# DomOS_V2.net
KiCad netlist of a schematic drawn in EAGLE
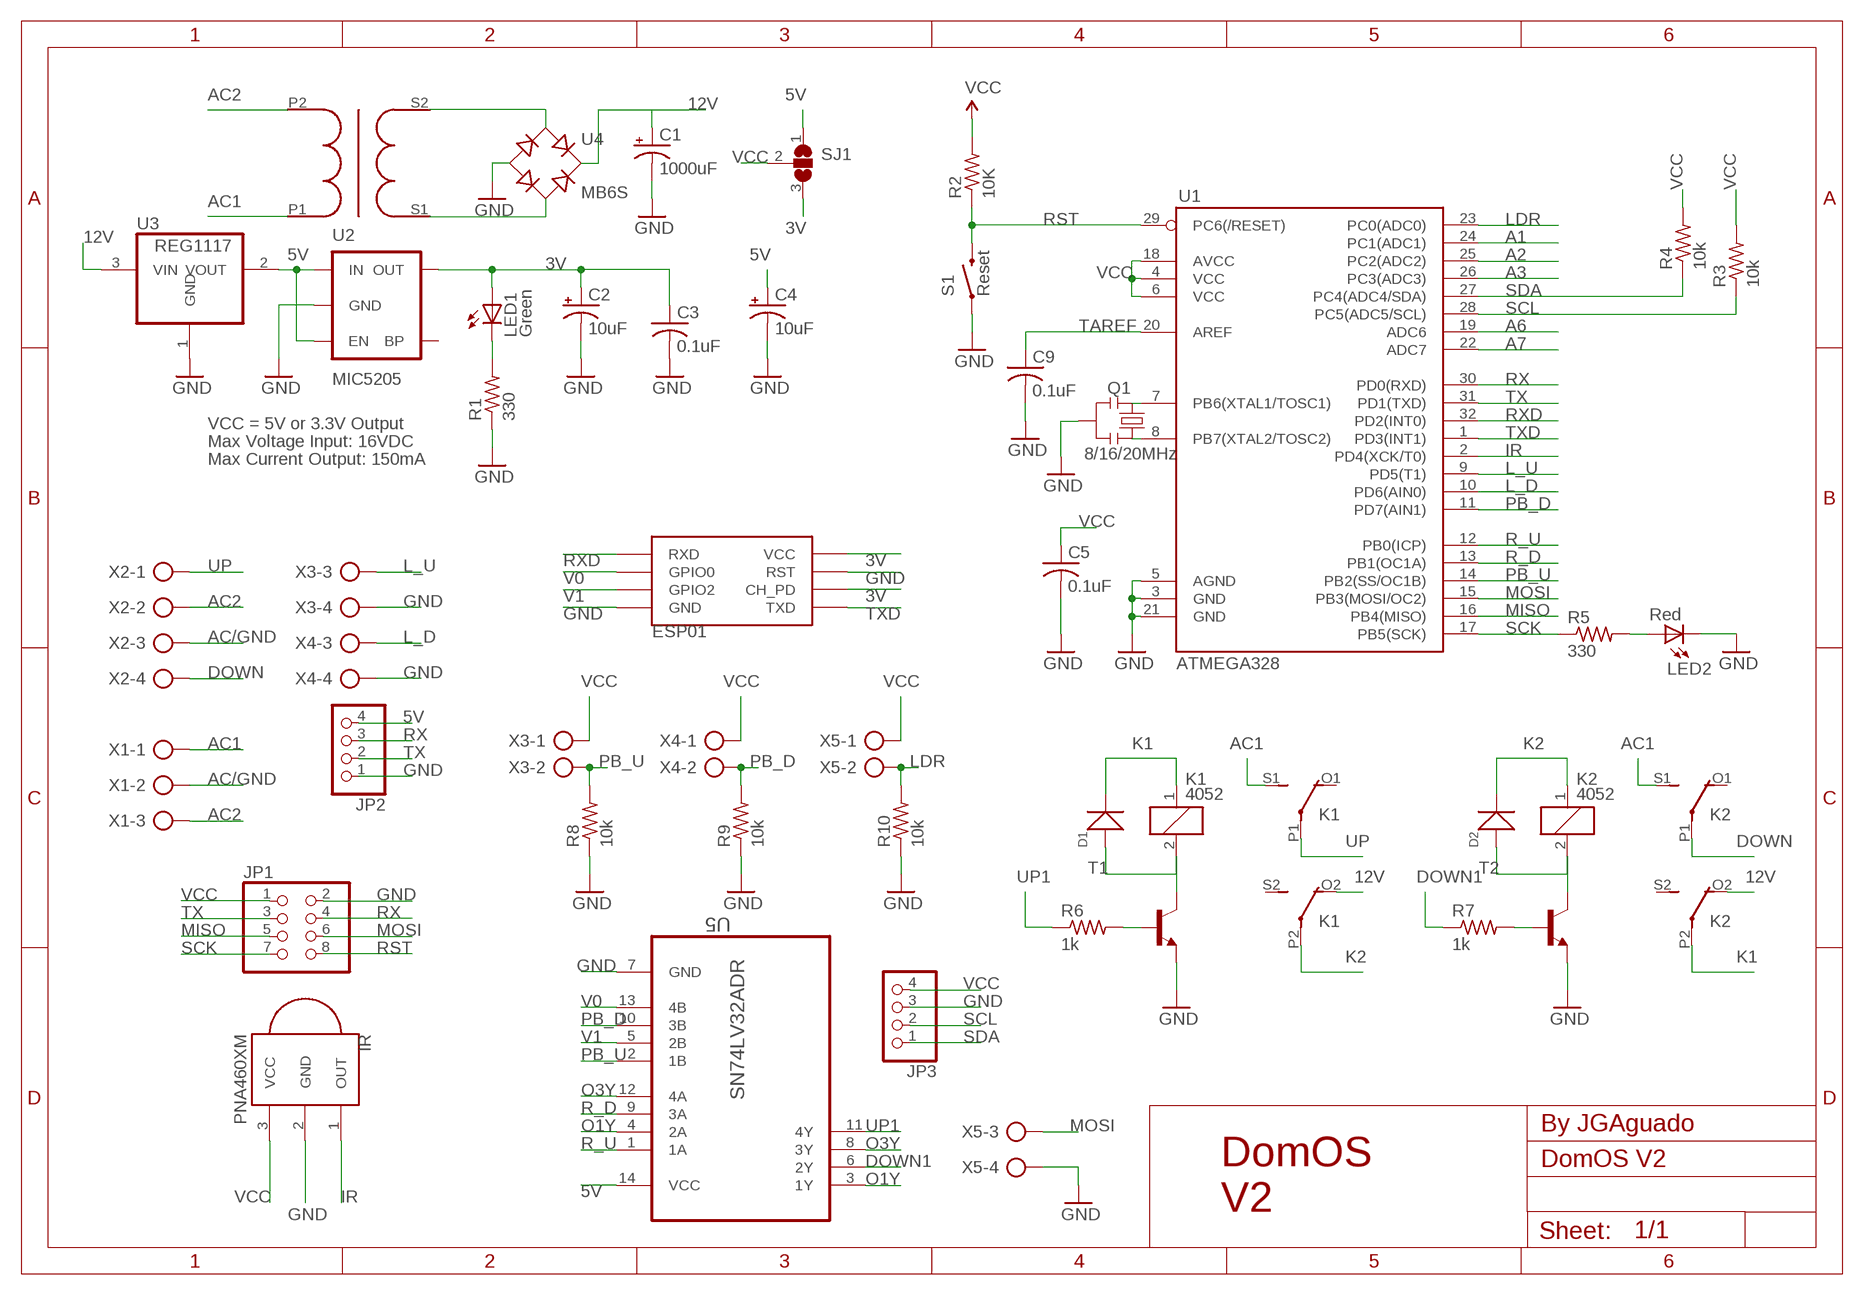
[diagram p0: schematic, sheet 1]

(export (version "E")
  (design (tool "Eeschema 10.0.6"))
  (components
    (comp (ref "C1")
      (value "1000uF")
      (footprint "eagle-import:140CLH-0810")
      (libsource (lib "eagle-import") (part "CPOL-US140CLH-0810"))
    )
    (comp (ref "C2")
      (value "10uF")
      (footprint "eagle-import:EIA3216")
      (libsource (lib "eagle-import") (part "CAP_POL1206"))
    )
    (comp (ref "C3")
      (value "0.1uF")
      (footprint "eagle-import:C1206")
      (libsource (lib "eagle-import") (part "C-USC1206"))
    )
    (comp (ref "C4")
      (value "10uF")
      (footprint "eagle-import:EIA3216")
      (libsource (lib "eagle-import") (part "CAP_POL1206"))
    )
    (comp (ref "C5")
      (value "0.1uF")
      (footprint "eagle-import:C1206")
      (libsource (lib "eagle-import") (part "C-USC1206"))
    )
    (comp (ref "C9")
      (value "0.1uF")
      (footprint "eagle-import:C1206")
      (libsource (lib "eagle-import") (part "C-USC1206"))
    )
    (comp (ref "D1")
      (value "SMD-DIODE-SWITCHING-75V-150MA(D1206)")
      (footprint "eagle-import:LED-1206")
      (fields (field (name "MPN") "CD1206-S01575"))
      (libsource (lib "eagle-import") (part "SMD-DIODE-SWITCHING-75V-150MA(D1206)"))
    )
    (comp (ref "D2")
      (value "SMD-DIODE-SWITCHING-75V-150MA(D1206)")
      (footprint "eagle-import:LED-1206")
      (fields (field (name "MPN") "CD1206-S01575"))
      (libsource (lib "eagle-import") (part "SMD-DIODE-SWITCHING-75V-150MA(D1206)"))
    )
    (comp (ref "ESP01")
      (value "ESP01")
      (footprint "eagle-import:ESP01")
      (libsource (lib "eagle-import") (part "ESP01"))
    )
    (comp (ref "IR")
      (value "PNA460XM")
      (footprint "eagle-import:PNA460XM")
      (libsource (lib "eagle-import") (part "PNA460XM"))
    )
    (comp (ref "JP1")
      (value "PINHD-2X4")
      (footprint "eagle-import:2X04")
      (libsource (lib "eagle-import") (part "PINHD-2X4"))
    )
    (comp (ref "JP2")
      (value "PINHD-1X4")
      (footprint "eagle-import:1X04")
      (libsource (lib "eagle-import") (part "PINHD-1X4"))
    )
    (comp (ref "JP3")
      (value "PINHD-1X4")
      (footprint "eagle-import:1X04")
      (libsource (lib "eagle-import") (part "PINHD-1X4"))
    )
    (comp (ref "K1")
      (value "4052")
      (footprint "eagle-import:F4052")
      (libsource (lib "eagle-import") (part "4052"))
    )
    (comp (ref "K2")
      (value "4052")
      (footprint "eagle-import:F4052")
      (libsource (lib "eagle-import") (part "4052"))
    )
    (comp (ref "LED1")
      (value "Green")
      (footprint "eagle-import:1206")
      (libsource (lib "eagle-import") (part "LEDSMT1206"))
    )
    (comp (ref "LED2")
      (value "Red")
      (footprint "eagle-import:1206")
      (libsource (lib "eagle-import") (part "LEDSMT1206"))
    )
    (comp (ref "Q1")
      (value "8/16/20MHz")
      (footprint "eagle-import:RESONATOR-SMD")
      (libsource (lib "eagle-import") (part "RESONATORSMD"))
    )
    (comp (ref "R1")
      (value "330")
      (footprint "eagle-import:R1206")
      (libsource (lib "eagle-import") (part "R-US_R1206"))
    )
    (comp (ref "R2")
      (value "10K")
      (footprint "eagle-import:R1206")
      (libsource (lib "eagle-import") (part "R-US_R1206"))
    )
    (comp (ref "R3")
      (value "10k")
      (footprint "eagle-import:R1206")
      (libsource (lib "eagle-import") (part "R-US_R1206"))
    )
    (comp (ref "R4")
      (value "10k")
      (footprint "eagle-import:R1206")
      (libsource (lib "eagle-import") (part "R-US_R1206"))
    )
    (comp (ref "R5")
      (value "330")
      (footprint "eagle-import:R1206")
      (libsource (lib "eagle-import") (part "R-US_R1206"))
    )
    (comp (ref "R6")
      (value "1k")
      (footprint "eagle-import:R1206")
      (libsource (lib "eagle-import") (part "R-US_R1206"))
    )
    (comp (ref "R7")
      (value "1k")
      (footprint "eagle-import:R1206")
      (libsource (lib "eagle-import") (part "R-US_R1206"))
    )
    (comp (ref "R8")
      (value "10k")
      (footprint "eagle-import:R1206")
      (libsource (lib "eagle-import") (part "R-US_R1206"))
    )
    (comp (ref "R9")
      (value "10k")
      (footprint "eagle-import:R1206")
      (libsource (lib "eagle-import") (part "R-US_R1206"))
    )
    (comp (ref "R10")
      (value "10k")
      (footprint "eagle-import:R1206")
      (libsource (lib "eagle-import") (part "R-US_R1206"))
    )
    (comp (ref "S1")
      (value "Reset")
      (footprint "eagle-import:TACTILE_SWITCH_TALL")
      (libsource (lib "eagle-import") (part "SWITCH-MOMENTARY-2SMD-4"))
    )
    (comp (ref "SJ1")
      (value "SJ2W")
      (footprint "eagle-import:SJ_2")
      (libsource (lib "eagle-import") (part "SJ2W"))
    )
    (comp (ref "T1")
      (value "BC817-16-NPN-SOT23-BEC")
      (footprint "eagle-import:SOT23-BEC")
      (libsource (lib "eagle-import") (part "-NPN-SOT23-BECBC817-16"))
    )
    (comp (ref "T2")
      (value "BC817-16-NPN-SOT23-BEC")
      (footprint "eagle-import:SOT23-BEC")
      (libsource (lib "eagle-import") (part "-NPN-SOT23-BECBC817-16"))
    )
    (comp (ref "U$1")
      (value "TRANSFORMADOR_PE3010-M")
      (footprint "eagle-import:TRANSFORMADOR_PE3010-M")
      (libsource (lib "eagle-import") (part "TRANSFORMADOR_PE3010-M"))
    )
    (comp (ref "U1")
      (value "ATMEGA328")
      (footprint "eagle-import:TQFP32-08")
      (libsource (lib "eagle-import") (part "ATMEGA168"))
    )
    (comp (ref "U2")
      (value "MIC5205")
      (footprint "eagle-import:SOT23-5")
      (libsource (lib "eagle-import") (part "V_REG_LDOSMD"))
    )
    (comp (ref "U3")
      (value "REG1117")
      (footprint "eagle-import:SOT223")
      (libsource (lib "eagle-import") (part "REG1117"))
    )
    (comp (ref "U4")
      (value "MB6S")
      (footprint "eagle-import:SOIC-4")
      (libsource (lib "eagle-import") (part "MBS6"))
    )
    (comp (ref "U5")
      (value "SN74LV32ADR")
      (footprint "eagle-import:SOIC127P600X175-14N")
      (fields (field (name "MPN") "SN74S32D"))
      (libsource (lib "eagle-import") (part "SN74S32D"))
    )
    (comp (ref "X1")
      (value "AK500/3")
      (footprint "eagle-import:AK500_3")
      (libsource (lib "eagle-import") (part "AK500/3"))
    )
    (comp (ref "X2")
      (value "AK500/4")
      (footprint "eagle-import:AK500_4")
      (libsource (lib "eagle-import") (part "AK500/4"))
    )
    (comp (ref "X3")
      (value "AK500/4")
      (footprint "eagle-import:AK500_4")
      (libsource (lib "eagle-import") (part "AK500/4"))
    )
    (comp (ref "X4")
      (value "AK500/4")
      (footprint "eagle-import:AK500_4")
      (libsource (lib "eagle-import") (part "AK500/4"))
    )
    (comp (ref "X5")
      (value "AK500/4")
      (footprint "eagle-import:AK500_4")
      (libsource (lib "eagle-import") (part "AK500/4"))
    )
  )
  (nets
    (net (code "1") (name "/3V") (class "Default")
      (node (ref "C2") (pin "A") (pinfunction "+_A") (pintype "passive"))
      (node (ref "C3") (pin "1") (pinfunction "1_1") (pintype "passive"))
      (node (ref "ESP01") (pin "CH_PD") (pinfunction "CH_PD_CH_PD") (pintype "bidirectional"))
      (node (ref "ESP01") (pin "VCC") (pinfunction "VCC_VCC") (pintype "bidirectional"))
      (node (ref "LED1") (pin "A") (pinfunction "A_A") (pintype "passive"))
      (node (ref "SJ1") (pin "3") (pinfunction "3_3") (pintype "passive"))
      (node (ref "U2") (pin "5") (pinfunction "OUT_5") (pintype "passive"))
    )
    (net (code "2") (name "/5V") (class "Default")
      (node (ref "C4") (pin "A") (pinfunction "+_A") (pintype "passive"))
      (node (ref "JP2") (pin "4") (pinfunction "4_4") (pintype "passive"))
      (node (ref "SJ1") (pin "1") (pinfunction "1_1") (pintype "passive"))
      (node (ref "U2") (pin "1") (pinfunction "IN_1") (pintype "input"))
      (node (ref "U2") (pin "3") (pinfunction "EN_3") (pintype "input"))
      (node (ref "U3") (pin "2") (pinfunction "VOUT_2") (pintype "output"))
      (node (ref "U5") (pin "14") (pinfunction "VCC_14") (pintype "power_in"))
    )
    (net (code "3") (name "/12V") (class "Default")
      (node (ref "C1") (pin "+") (pinfunction "+_+") (pintype "passive"))
      (node (ref "K1") (pin "O2") (pinfunction "O_O2") (pintype "passive"))
      (node (ref "K2") (pin "O2") (pinfunction "O_O2") (pintype "passive"))
      (node (ref "U3") (pin "3") (pinfunction "VIN_3") (pintype "input"))
      (node (ref "U4") (pin "+") (pinfunction "+_+") (pintype "passive"))
    )
    (net (code "4") (name "/A1") (class "Default")
      (node (ref "U1") (pin "24") (pinfunction "PC1(ADC1)_24") (pintype "bidirectional"))
    )
    (net (code "5") (name "/A2") (class "Default")
      (node (ref "U1") (pin "25") (pinfunction "PC2(ADC2)_25") (pintype "bidirectional"))
    )
    (net (code "6") (name "/A3") (class "Default")
      (node (ref "U1") (pin "26") (pinfunction "PC3(ADC3)_26") (pintype "bidirectional"))
    )
    (net (code "7") (name "/A6") (class "Default")
      (node (ref "U1") (pin "19") (pinfunction "ADC6_19") (pintype "bidirectional"))
    )
    (net (code "8") (name "/A7") (class "Default")
      (node (ref "U1") (pin "22") (pinfunction "ADC7_22") (pintype "bidirectional"))
    )
    (net (code "9") (name "/AC1") (class "Default")
      (node (ref "K1") (pin "S1") (pinfunction "S_S1") (pintype "passive"))
      (node (ref "K2") (pin "S1") (pinfunction "S_S1") (pintype "passive"))
      (node (ref "U$1") (pin "P1") (pinfunction "P1_P1") (pintype "bidirectional"))
      (node (ref "X1") (pin "1") (pinfunction "KL_1") (pintype "passive"))
    )
    (net (code "10") (name "/AC2") (class "Default")
      (node (ref "U$1") (pin "P2") (pinfunction "P2_P2") (pintype "bidirectional"))
      (node (ref "X1") (pin "3") (pinfunction "KL_3") (pintype "passive"))
      (node (ref "X2") (pin "2") (pinfunction "KL_2") (pintype "passive"))
    )
    (net (code "11") (name "/AC{slash}GND") (class "Default")
      (node (ref "X1") (pin "2") (pinfunction "KL_2") (pintype "passive"))
      (node (ref "X2") (pin "3") (pinfunction "KL_3") (pintype "passive"))
    )
    (net (code "12") (name "/DOWN") (class "Default")
      (node (ref "K2") (pin "P1") (pinfunction "P_P1") (pintype "passive"))
      (node (ref "X2") (pin "4") (pinfunction "KL_4") (pintype "passive"))
    )
    (net (code "13") (name "/DOWN1") (class "Default")
      (node (ref "R7") (pin "1") (pinfunction "1_1") (pintype "passive"))
      (node (ref "U5") (pin "6") (pinfunction "2Y_6") (pintype "output"))
    )
    (net (code "14") (name "/IR") (class "Default")
      (node (ref "IR") (pin "1") (pinfunction "OUT_1") (pintype "output"))
      (node (ref "U1") (pin "2") (pinfunction "PD4(XCK/T0)_2") (pintype "bidirectional"))
    )
    (net (code "15") (name "/K1") (class "Default")
      (node (ref "D1") (pin "-") (pinfunction "-_-") (pintype "passive"))
      (node (ref "K1") (pin "1") (pinfunction "1_1") (pintype "passive"))
      (node (ref "K2") (pin "P2") (pinfunction "P_P2") (pintype "passive"))
    )
    (net (code "16") (name "/K2") (class "Default")
      (node (ref "D2") (pin "-") (pinfunction "-_-") (pintype "passive"))
      (node (ref "K1") (pin "P2") (pinfunction "P_P2") (pintype "passive"))
      (node (ref "K2") (pin "1") (pinfunction "1_1") (pintype "passive"))
    )
    (net (code "17") (name "/LDR") (class "Default")
      (node (ref "R10") (pin "2") (pinfunction "2_2") (pintype "passive"))
      (node (ref "U1") (pin "23") (pinfunction "PC0(ADC0)_23") (pintype "bidirectional"))
      (node (ref "X5") (pin "2") (pinfunction "KL_2") (pintype "passive"))
    )
    (net (code "18") (name "/L_D") (class "Default")
      (node (ref "U1") (pin "10") (pinfunction "PD6(AIN0)_10") (pintype "bidirectional"))
      (node (ref "X4") (pin "3") (pinfunction "KL_3") (pintype "passive"))
    )
    (net (code "19") (name "/L_U") (class "Default")
      (node (ref "U1") (pin "9") (pinfunction "PD5(T1)_9") (pintype "bidirectional"))
      (node (ref "X3") (pin "3") (pinfunction "KL_3") (pintype "passive"))
    )
    (net (code "20") (name "/MISO") (class "Default")
      (node (ref "JP1") (pin "5") (pinfunction "5_5") (pintype "passive"))
      (node (ref "U1") (pin "16") (pinfunction "PB4(MISO)_16") (pintype "bidirectional"))
    )
    (net (code "21") (name "/MOSI") (class "Default")
      (node (ref "JP1") (pin "6") (pinfunction "6_6") (pintype "passive"))
      (node (ref "U1") (pin "15") (pinfunction "PB3(MOSI/OC2)_15") (pintype "bidirectional"))
      (node (ref "X5") (pin "3") (pinfunction "KL_3") (pintype "passive"))
    )
    (net (code "22") (name "/O1Y") (class "Default")
      (node (ref "U5") (pin "3") (pinfunction "1Y_3") (pintype "output"))
      (node (ref "U5") (pin "4") (pinfunction "2A_4") (pintype "input"))
    )
    (net (code "23") (name "/O3Y") (class "Default")
      (node (ref "U5") (pin "12") (pinfunction "4A_12") (pintype "input"))
      (node (ref "U5") (pin "8") (pinfunction "3Y_8") (pintype "output"))
    )
    (net (code "24") (name "/PB_D") (class "Default")
      (node (ref "R9") (pin "2") (pinfunction "2_2") (pintype "passive"))
      (node (ref "U1") (pin "11") (pinfunction "PD7(AIN1)_11") (pintype "bidirectional"))
      (node (ref "U5") (pin "10") (pinfunction "3B_10") (pintype "input"))
      (node (ref "X4") (pin "2") (pinfunction "KL_2") (pintype "passive"))
    )
    (net (code "25") (name "/PB_U") (class "Default")
      (node (ref "R8") (pin "2") (pinfunction "2_2") (pintype "passive"))
      (node (ref "U1") (pin "14") (pinfunction "PB2(SS/OC1B)_14") (pintype "bidirectional"))
      (node (ref "U5") (pin "2") (pinfunction "1B_2") (pintype "input"))
      (node (ref "X3") (pin "2") (pinfunction "KL_2") (pintype "passive"))
    )
    (net (code "26") (name "/RST") (class "Default")
      (node (ref "JP1") (pin "8") (pinfunction "8_8") (pintype "passive"))
      (node (ref "R2") (pin "1") (pinfunction "1_1") (pintype "passive"))
      (node (ref "S1") (pin "B2") (pinfunction "2_B2") (pintype "passive"))
      (node (ref "U1") (pin "29") (pinfunction "PC6(/RESET)_29") (pintype "bidirectional"))
    )
    (net (code "27") (name "/RX") (class "Default")
      (node (ref "JP1") (pin "4") (pinfunction "4_4") (pintype "passive"))
      (node (ref "JP2") (pin "3") (pinfunction "3_3") (pintype "passive"))
      (node (ref "U1") (pin "30") (pinfunction "PD0(RXD)_30") (pintype "bidirectional"))
    )
    (net (code "28") (name "/RXD") (class "Default")
      (node (ref "ESP01") (pin "RX") (pinfunction "RXD_RX") (pintype "bidirectional"))
      (node (ref "U1") (pin "32") (pinfunction "PD2(INT0)_32") (pintype "bidirectional"))
    )
    (net (code "29") (name "/R_D") (class "Default")
      (node (ref "U1") (pin "13") (pinfunction "PB1(OC1A)_13") (pintype "bidirectional"))
      (node (ref "U5") (pin "9") (pinfunction "3A_9") (pintype "input"))
    )
    (net (code "30") (name "/R_U") (class "Default")
      (node (ref "U1") (pin "12") (pinfunction "PB0(ICP)_12") (pintype "bidirectional"))
      (node (ref "U5") (pin "1") (pinfunction "1A_1") (pintype "input"))
    )
    (net (code "31") (name "/SCK") (class "Default")
      (node (ref "JP1") (pin "7") (pinfunction "7_7") (pintype "passive"))
      (node (ref "R5") (pin "1") (pinfunction "1_1") (pintype "passive"))
      (node (ref "U1") (pin "17") (pinfunction "PB5(SCK)_17") (pintype "bidirectional"))
    )
    (net (code "32") (name "/SCL") (class "Default")
      (node (ref "JP3") (pin "2") (pinfunction "2_2") (pintype "passive"))
      (node (ref "R3") (pin "1") (pinfunction "1_1") (pintype "passive"))
      (node (ref "U1") (pin "28") (pinfunction "PC5(ADC5/SCL)_28") (pintype "bidirectional"))
    )
    (net (code "33") (name "/SDA") (class "Default")
      (node (ref "JP3") (pin "1") (pinfunction "1_1") (pintype "passive"))
      (node (ref "R4") (pin "1") (pinfunction "1_1") (pintype "passive"))
      (node (ref "U1") (pin "27") (pinfunction "PC4(ADC4/SDA)_27") (pintype "bidirectional"))
    )
    (net (code "34") (name "/TAREF") (class "Default")
      (node (ref "C9") (pin "1") (pinfunction "1_1") (pintype "passive"))
      (node (ref "U1") (pin "20") (pinfunction "AREF_20") (pintype "bidirectional"))
    )
    (net (code "35") (name "/TX") (class "Default")
      (node (ref "JP1") (pin "3") (pinfunction "3_3") (pintype "passive"))
      (node (ref "JP2") (pin "2") (pinfunction "2_2") (pintype "passive"))
      (node (ref "U1") (pin "31") (pinfunction "PD1(TXD)_31") (pintype "bidirectional"))
    )
    (net (code "36") (name "/TXD") (class "Default")
      (node (ref "ESP01") (pin "TX") (pinfunction "TXD_TX") (pintype "bidirectional"))
      (node (ref "U1") (pin "1") (pinfunction "PD3(INT1)_1") (pintype "bidirectional"))
    )
    (net (code "37") (name "/UP") (class "Default")
      (node (ref "K1") (pin "P1") (pinfunction "P_P1") (pintype "passive"))
      (node (ref "X2") (pin "1") (pinfunction "KL_1") (pintype "passive"))
    )
    (net (code "38") (name "/UP1") (class "Default")
      (node (ref "R6") (pin "1") (pinfunction "1_1") (pintype "passive"))
      (node (ref "U5") (pin "11") (pinfunction "4Y_11") (pintype "output"))
    )
    (net (code "39") (name "/V0") (class "Default")
      (node (ref "ESP01") (pin "GPIO0") (pinfunction "GPIO0_GPIO0") (pintype "bidirectional"))
      (node (ref "U5") (pin "13") (pinfunction "4B_13") (pintype "input"))
    )
    (net (code "40") (name "/V1") (class "Default")
      (node (ref "ESP01") (pin "GPIO2") (pinfunction "GPIO2_GPIO2") (pintype "bidirectional"))
      (node (ref "U5") (pin "5") (pinfunction "2B_5") (pintype "input"))
    )
    (net (code "41") (name "GND") (class "Default")
      (node (ref "C1") (pin "-") (pinfunction "-_-") (pintype "passive"))
      (node (ref "C2") (pin "C") (pinfunction "-_C") (pintype "passive"))
      (node (ref "C3") (pin "2") (pinfunction "2_2") (pintype "passive"))
      (node (ref "C4") (pin "C") (pinfunction "-_C") (pintype "passive"))
      (node (ref "C5") (pin "2") (pinfunction "2_2") (pintype "passive"))
      (node (ref "C9") (pin "2") (pinfunction "2_2") (pintype "passive"))
      (node (ref "ESP01") (pin "GND") (pinfunction "GND_GND") (pintype "bidirectional"))
      (node (ref "ESP01") (pin "RST") (pinfunction "RST_RST") (pintype "bidirectional"))
      (node (ref "IR") (pin "2") (pinfunction "GND_2") (pintype "power_in"))
      (node (ref "JP1") (pin "2") (pinfunction "2_2") (pintype "passive"))
      (node (ref "JP2") (pin "1") (pinfunction "1_1") (pintype "passive"))
      (node (ref "JP3") (pin "3") (pinfunction "3_3") (pintype "passive"))
      (node (ref "LED2") (pin "C") (pinfunction "C_C") (pintype "passive"))
      (node (ref "Q1") (pin "2") (pinfunction "2_2") (pintype "passive"))
      (node (ref "R1") (pin "1") (pinfunction "1_1") (pintype "passive"))
      (node (ref "R10") (pin "1") (pinfunction "1_1") (pintype "passive"))
      (node (ref "R8") (pin "1") (pinfunction "1_1") (pintype "passive"))
      (node (ref "R9") (pin "1") (pinfunction "1_1") (pintype "passive"))
      (node (ref "S1") (pin "A2") (pinfunction "1_A2") (pintype "passive"))
      (node (ref "T1") (pin "E") (pinfunction "E_E") (pintype "passive"))
      (node (ref "T2") (pin "E") (pinfunction "E_E") (pintype "passive"))
      (node (ref "U1") (pin "21") (pinfunction "GND_21") (pintype "bidirectional"))
      (node (ref "U1") (pin "3") (pinfunction "GND_3") (pintype "bidirectional"))
      (node (ref "U1") (pin "5") (pinfunction "AGND_5") (pintype "bidirectional"))
      (node (ref "U2") (pin "2") (pinfunction "GND_2") (pintype "input"))
      (node (ref "U3") (pin "1") (pinfunction "GND_1") (pintype "power_in"))
      (node (ref "U4") (pin "-") (pinfunction "-_-") (pintype "passive"))
      (node (ref "U5") (pin "7") (pinfunction "GND_7") (pintype "passive"))
      (node (ref "X3") (pin "4") (pinfunction "KL_4") (pintype "passive"))
      (node (ref "X4") (pin "4") (pinfunction "KL_4") (pintype "passive"))
      (node (ref "X5") (pin "4") (pinfunction "KL_4") (pintype "passive"))
    )
    (net (code "42") (name "Net-(D1-Pad+)") (class "Default")
      (node (ref "D1") (pin "+") (pinfunction "+_+") (pintype "passive"))
      (node (ref "K1") (pin "2") (pinfunction "2_2") (pintype "passive"))
      (node (ref "T1") (pin "C") (pinfunction "C_C") (pintype "passive"))
    )
    (net (code "43") (name "Net-(D2-Pad+)") (class "Default")
      (node (ref "D2") (pin "+") (pinfunction "+_+") (pintype "passive"))
      (node (ref "K2") (pin "2") (pinfunction "2_2") (pintype "passive"))
      (node (ref "T2") (pin "C") (pinfunction "C_C") (pintype "passive"))
    )
    (net (code "44") (name "Net-(LED1-PadC)") (class "Default")
      (node (ref "LED1") (pin "C") (pinfunction "C_C") (pintype "passive"))
      (node (ref "R1") (pin "2") (pinfunction "2_2") (pintype "passive"))
    )
    (net (code "45") (name "Net-(LED2-PadA)") (class "Default")
      (node (ref "LED2") (pin "A") (pinfunction "A_A") (pintype "passive"))
      (node (ref "R5") (pin "2") (pinfunction "2_2") (pintype "passive"))
    )
    (net (code "46") (name "Net-(R6-Pad2)") (class "Default")
      (node (ref "R6") (pin "2") (pinfunction "2_2") (pintype "passive"))
      (node (ref "T1") (pin "B") (pinfunction "B_B") (pintype "passive"))
    )
    (net (code "47") (name "Net-(R7-Pad2)") (class "Default")
      (node (ref "R7") (pin "2") (pinfunction "2_2") (pintype "passive"))
      (node (ref "T2") (pin "B") (pinfunction "B_B") (pintype "passive"))
    )
    (net (code "48") (name "Net-(U1-PB6(XTAL1{slash}TOSC1))") (class "Default")
      (node (ref "Q1") (pin "1") (pinfunction "1_1") (pintype "passive"))
      (node (ref "U1") (pin "7") (pinfunction "PB6(XTAL1/TOSC1)_7") (pintype "bidirectional"))
    )
    (net (code "49") (name "Net-(U1-PB7(XTAL2{slash}TOSC2))") (class "Default")
      (node (ref "Q1") (pin "3") (pinfunction "3_3") (pintype "passive"))
      (node (ref "U1") (pin "8") (pinfunction "PB7(XTAL2/TOSC2)_8") (pintype "bidirectional"))
    )
    (net (code "50") (name "Net-(U4-AC1)") (class "Default")
      (node (ref "U$1") (pin "S2") (pinfunction "S2_S2") (pintype "bidirectional"))
      (node (ref "U4") (pin "~1") (pinfunction "AC1_~1") (pintype "passive"))
    )
    (net (code "51") (name "Net-(U4-AC2)") (class "Default")
      (node (ref "U$1") (pin "S1") (pinfunction "S1_S1") (pintype "bidirectional"))
      (node (ref "U4") (pin "~2") (pinfunction "AC2_~2") (pintype "passive"))
    )
    (net (code "52") (name "VCC") (class "Default")
      (node (ref "C5") (pin "1") (pinfunction "1_1") (pintype "passive"))
      (node (ref "IR") (pin "3") (pinfunction "VCC_3") (pintype "power_in"))
      (node (ref "JP1") (pin "1") (pinfunction "1_1") (pintype "passive"))
      (node (ref "JP3") (pin "4") (pinfunction "4_4") (pintype "passive"))
      (node (ref "R2") (pin "2") (pinfunction "2_2") (pintype "passive"))
      (node (ref "R3") (pin "2") (pinfunction "2_2") (pintype "passive"))
      (node (ref "R4") (pin "2") (pinfunction "2_2") (pintype "passive"))
      (node (ref "SJ1") (pin "2") (pinfunction "2_2") (pintype "passive"))
      (node (ref "U1") (pin "18") (pinfunction "AVCC_18") (pintype "bidirectional"))
      (node (ref "U1") (pin "4") (pinfunction "VCC_4") (pintype "bidirectional"))
      (node (ref "U1") (pin "6") (pinfunction "VCC_6") (pintype "bidirectional"))
      (node (ref "X3") (pin "1") (pinfunction "KL_1") (pintype "passive"))
      (node (ref "X4") (pin "1") (pinfunction "KL_1") (pintype "passive"))
      (node (ref "X5") (pin "1") (pinfunction "KL_1") (pintype "passive"))
    )
    (net (code "53") (name "unconnected-(K1B-O-PadO1)") (class "Default")
      (node (ref "K1") (pin "O1") (pinfunction "O_O1") (pintype "passive"))
    )
    (net (code "54") (name "unconnected-(K1C-S-PadS2)") (class "Default")
      (node (ref "K1") (pin "S2") (pinfunction "S_S2") (pintype "passive"))
    )
    (net (code "55") (name "unconnected-(K2B-O-PadO1)") (class "Default")
      (node (ref "K2") (pin "O1") (pinfunction "O_O1") (pintype "passive"))
    )
    (net (code "56") (name "unconnected-(K2C-S-PadS2)") (class "Default")
      (node (ref "K2") (pin "S2") (pinfunction "S_S2") (pintype "passive"))
    )
    (net (code "57") (name "unconnected-(U2-BP-Pad4)") (class "Default")
      (node (ref "U2") (pin "4") (pinfunction "BP_4") (pintype "input"))
    )
  )
)
